# 04_SDRAM.net
KiCad netlist of a schematic drawn in Altium Designer
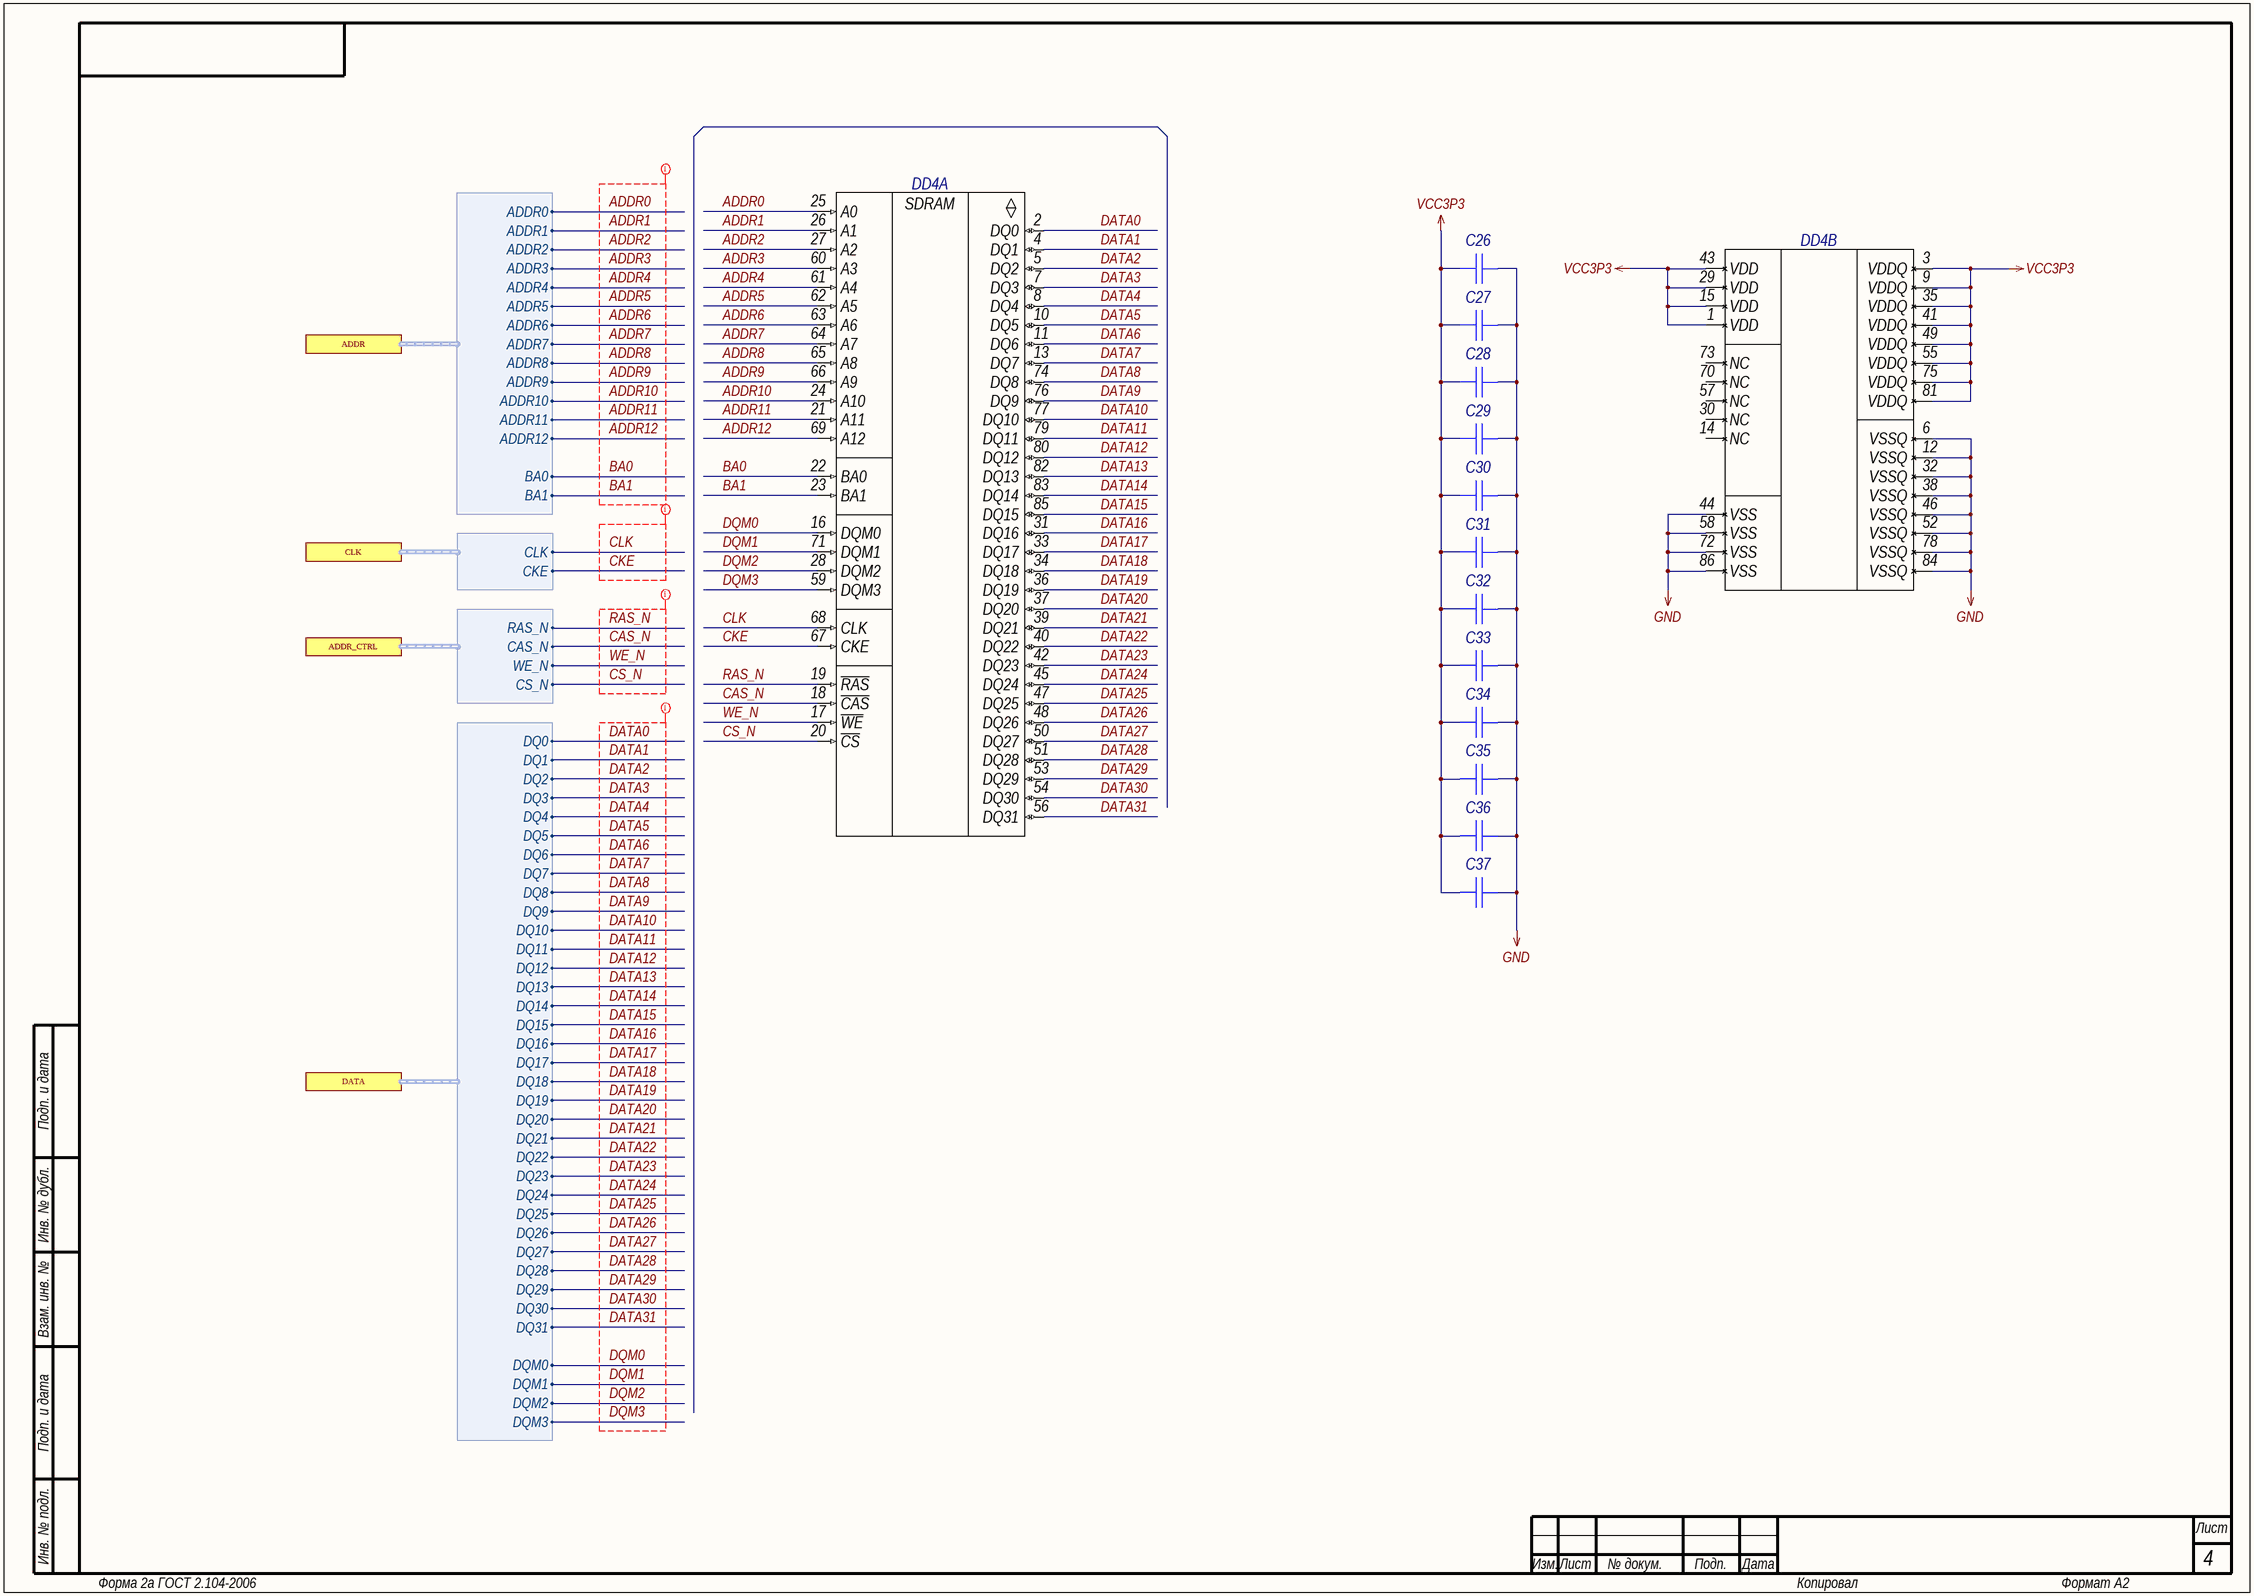
[diagram p0: 04_SDRAM.SchDoc]

(export (version "E")
  (design (tool "Eeschema 10.0.6"))
  (components
    (comp (ref "C26")
      (value "Capacitor")
      (footprint "C0402_L")
      (fields
        (field (name "PART NUMBER") "GRM155R60J106ME15D")
        (field (name "VOLTAGE") "6.3V")
        (field (name "TOLERANCE") "±20%")
        (field (name "PUBLISHER") "Andrew Danich")
      )
      (libsource (lib "ADLib") (part "Capacitor"))
    )
    (comp (ref "C27")
      (value "Capacitor")
      (footprint "C0402_L")
      (fields
        (field (name "PART NUMBER") "GRM155R60J106ME15D")
        (field (name "VOLTAGE") "6.3V")
        (field (name "TOLERANCE") "±20%")
        (field (name "PUBLISHER") "Andrew Danich")
      )
      (libsource (lib "ADLib") (part "Capacitor"))
    )
    (comp (ref "C28")
      (value "Capacitor")
      (footprint "C0402_L")
      (fields
        (field (name "PART NUMBER") "GCM155R71C104KA55D")
        (field (name "VOLTAGE") "16V")
        (field (name "TOLERANCE") "±10%")
        (field (name "PUBLISHER") "Andrew Danich")
      )
      (libsource (lib "ADLib") (part "Capacitor"))
    )
    (comp (ref "C29")
      (value "Capacitor")
      (footprint "C0402_L")
      (fields
        (field (name "PART NUMBER") "GCM155R71C104KA55D")
        (field (name "VOLTAGE") "16V")
        (field (name "TOLERANCE") "±10%")
        (field (name "PUBLISHER") "Andrew Danich")
      )
      (libsource (lib "ADLib") (part "Capacitor"))
    )
    (comp (ref "C30")
      (value "Capacitor")
      (footprint "C0402_L")
      (fields
        (field (name "PART NUMBER") "GCM155R71C104KA55D")
        (field (name "VOLTAGE") "16V")
        (field (name "TOLERANCE") "±10%")
        (field (name "PUBLISHER") "Andrew Danich")
      )
      (libsource (lib "ADLib") (part "Capacitor"))
    )
    (comp (ref "C31")
      (value "Capacitor")
      (footprint "C0402_L")
      (fields
        (field (name "PART NUMBER") "GCM155R71C104KA55D")
        (field (name "VOLTAGE") "16V")
        (field (name "TOLERANCE") "±10%")
        (field (name "PUBLISHER") "Andrew Danich")
      )
      (libsource (lib "ADLib") (part "Capacitor"))
    )
    (comp (ref "C32")
      (value "Capacitor")
      (footprint "C0402_L")
      (fields
        (field (name "PART NUMBER") "GCM155R71E103KA37D")
        (field (name "VOLTAGE") "25V")
        (field (name "TOLERANCE") "±10%")
        (field (name "PUBLISHER") "Andrew Danich")
      )
      (libsource (lib "ADLib") (part "Capacitor"))
    )
    (comp (ref "C33")
      (value "Capacitor")
      (footprint "C0402_L")
      (fields
        (field (name "PART NUMBER") "GCM155R71E103KA37D")
        (field (name "VOLTAGE") "25V")
        (field (name "TOLERANCE") "±10%")
        (field (name "PUBLISHER") "Andrew Danich")
      )
      (libsource (lib "ADLib") (part "Capacitor"))
    )
    (comp (ref "C34")
      (value "Capacitor")
      (footprint "C0402_L")
      (fields
        (field (name "PART NUMBER") "GCM155R71E103KA37D")
        (field (name "VOLTAGE") "25V")
        (field (name "TOLERANCE") "±10%")
        (field (name "PUBLISHER") "Andrew Danich")
      )
      (libsource (lib "ADLib") (part "Capacitor"))
    )
    (comp (ref "C35")
      (value "Capacitor")
      (footprint "C0402_L")
      (fields
        (field (name "PART NUMBER") "GCM155R71E103KA37D")
        (field (name "VOLTAGE") "25V")
        (field (name "TOLERANCE") "±10%")
        (field (name "PUBLISHER") "Andrew Danich")
      )
      (libsource (lib "ADLib") (part "Capacitor"))
    )
    (comp (ref "C36")
      (value "Capacitor")
      (footprint "C0402_L")
      (fields
        (field (name "PART NUMBER") "GCM155R71E103KA37D")
        (field (name "VOLTAGE") "25V")
        (field (name "TOLERANCE") "±10%")
        (field (name "PUBLISHER") "Andrew Danich")
      )
      (libsource (lib "ADLib") (part "Capacitor"))
    )
    (comp (ref "C37")
      (value "Capacitor")
      (footprint "C0402_L")
      (fields
        (field (name "PART NUMBER") "GCM155R71E103KA37D")
        (field (name "VOLTAGE") "25V")
        (field (name "TOLERANCE") "±10%")
        (field (name "PUBLISHER") "Andrew Danich")
      )
      (libsource (lib "ADLib") (part "Capacitor"))
    )
    (comp (ref "DD4")
      (value "IS4xS32160F-xTxx-Series")
      (footprint "TSOP2-86_050P2222X1016X125_N")
      (fields
        (field (name "PART NUMBER") "IS42S32160F-7TLI")
        (field (name "MANUFACTURER") "ISSI")
        (field (name "PUBLISHER") "Andrew Danich")
      )
      (libsource (lib "ADLib") (part "IS4xS32160F-xTxx-Series"))
    )
  )
  (nets
    (net (code "5") (name "/ADDR0") (class "Default")
      (node (ref "DD4") (pin "25") (pinfunction "A0_25") (pintype "input"))
    )
    (net (code "6") (name "/ADDR1") (class "Default")
      (node (ref "DD4") (pin "26") (pinfunction "A1_26") (pintype "input"))
    )
    (net (code "7") (name "/ADDR2") (class "Default")
      (node (ref "DD4") (pin "27") (pinfunction "A2_27") (pintype "input"))
    )
    (net (code "8") (name "/ADDR3") (class "Default")
      (node (ref "DD4") (pin "60") (pinfunction "A3_60") (pintype "input"))
    )
    (net (code "9") (name "/ADDR4") (class "Default")
      (node (ref "DD4") (pin "61") (pinfunction "A4_61") (pintype "input"))
    )
    (net (code "10") (name "/ADDR5") (class "Default")
      (node (ref "DD4") (pin "62") (pinfunction "A5_62") (pintype "input"))
    )
    (net (code "11") (name "/ADDR6") (class "Default")
      (node (ref "DD4") (pin "63") (pinfunction "A6_63") (pintype "input"))
    )
    (net (code "12") (name "/ADDR7") (class "Default")
      (node (ref "DD4") (pin "64") (pinfunction "A7_64") (pintype "input"))
    )
    (net (code "13") (name "/ADDR8") (class "Default")
      (node (ref "DD4") (pin "65") (pinfunction "A8_65") (pintype "input"))
    )
    (net (code "14") (name "/ADDR9") (class "Default")
      (node (ref "DD4") (pin "66") (pinfunction "A9_66") (pintype "input"))
    )
    (net (code "15") (name "/ADDR10") (class "Default")
      (node (ref "DD4") (pin "24") (pinfunction "A10_24") (pintype "input"))
    )
    (net (code "16") (name "/ADDR11") (class "Default")
      (node (ref "DD4") (pin "21") (pinfunction "A11_21") (pintype "input"))
    )
    (net (code "17") (name "/ADDR12") (class "Default")
      (node (ref "DD4") (pin "69") (pinfunction "A12_69") (pintype "input"))
    )
    (net (code "18") (name "/BA0") (class "Default")
      (node (ref "DD4") (pin "22") (pinfunction "BA0_22") (pintype "input"))
    )
    (net (code "19") (name "/BA1") (class "Default")
      (node (ref "DD4") (pin "23") (pinfunction "BA1_23") (pintype "input"))
    )
    (net (code "20") (name "/CAS_N") (class "Default")
      (node (ref "DD4") (pin "18") (pinfunction "~{CAS}_18") (pintype "input"))
    )
    (net (code "21") (name "/CKE") (class "Default")
      (node (ref "DD4") (pin "67") (pinfunction "CKE_67") (pintype "input"))
    )
    (net (code "22") (name "/CLK") (class "Default")
      (node (ref "DD4") (pin "68") (pinfunction "CLK_68") (pintype "input"))
    )
    (net (code "23") (name "/CS_N") (class "Default")
      (node (ref "DD4") (pin "20") (pinfunction "~{CS}_20") (pintype "input"))
    )
    (net (code "24") (name "/DATA0") (class "Default")
      (node (ref "DD4") (pin "2") (pinfunction "DQ0_2") (pintype "bidirectional"))
    )
    (net (code "25") (name "/DATA1") (class "Default")
      (node (ref "DD4") (pin "4") (pinfunction "DQ1_4") (pintype "bidirectional"))
    )
    (net (code "26") (name "/DATA2") (class "Default")
      (node (ref "DD4") (pin "5") (pinfunction "DQ2_5") (pintype "bidirectional"))
    )
    (net (code "27") (name "/DATA3") (class "Default")
      (node (ref "DD4") (pin "7") (pinfunction "DQ3_7") (pintype "bidirectional"))
    )
    (net (code "28") (name "/DATA4") (class "Default")
      (node (ref "DD4") (pin "8") (pinfunction "DQ4_8") (pintype "bidirectional"))
    )
    (net (code "29") (name "/DATA5") (class "Default")
      (node (ref "DD4") (pin "10") (pinfunction "DQ5_10") (pintype "bidirectional"))
    )
    (net (code "30") (name "/DATA6") (class "Default")
      (node (ref "DD4") (pin "11") (pinfunction "DQ6_11") (pintype "bidirectional"))
    )
    (net (code "31") (name "/DATA7") (class "Default")
      (node (ref "DD4") (pin "13") (pinfunction "DQ7_13") (pintype "bidirectional"))
    )
    (net (code "32") (name "/DATA8") (class "Default")
      (node (ref "DD4") (pin "74") (pinfunction "DQ8_74") (pintype "bidirectional"))
    )
    (net (code "33") (name "/DATA9") (class "Default")
      (node (ref "DD4") (pin "76") (pinfunction "DQ9_76") (pintype "bidirectional"))
    )
    (net (code "34") (name "/DATA10") (class "Default")
      (node (ref "DD4") (pin "77") (pinfunction "DQ10_77") (pintype "bidirectional"))
    )
    (net (code "35") (name "/DATA11") (class "Default")
      (node (ref "DD4") (pin "79") (pinfunction "DQ11_79") (pintype "bidirectional"))
    )
    (net (code "36") (name "/DATA12") (class "Default")
      (node (ref "DD4") (pin "80") (pinfunction "DQ12_80") (pintype "bidirectional"))
    )
    (net (code "37") (name "/DATA13") (class "Default")
      (node (ref "DD4") (pin "82") (pinfunction "DQ13_82") (pintype "bidirectional"))
    )
    (net (code "38") (name "/DATA14") (class "Default")
      (node (ref "DD4") (pin "83") (pinfunction "DQ14_83") (pintype "bidirectional"))
    )
    (net (code "39") (name "/DATA15") (class "Default")
      (node (ref "DD4") (pin "85") (pinfunction "DQ15_85") (pintype "bidirectional"))
    )
    (net (code "40") (name "/DATA16") (class "Default")
      (node (ref "DD4") (pin "31") (pinfunction "DQ16_31") (pintype "bidirectional"))
    )
    (net (code "41") (name "/DATA17") (class "Default")
      (node (ref "DD4") (pin "33") (pinfunction "DQ17_33") (pintype "bidirectional"))
    )
    (net (code "42") (name "/DATA18") (class "Default")
      (node (ref "DD4") (pin "34") (pinfunction "DQ18_34") (pintype "bidirectional"))
    )
    (net (code "43") (name "/DATA19") (class "Default")
      (node (ref "DD4") (pin "36") (pinfunction "DQ19_36") (pintype "bidirectional"))
    )
    (net (code "44") (name "/DATA20") (class "Default")
      (node (ref "DD4") (pin "37") (pinfunction "DQ20_37") (pintype "bidirectional"))
    )
    (net (code "45") (name "/DATA21") (class "Default")
      (node (ref "DD4") (pin "39") (pinfunction "DQ21_39") (pintype "bidirectional"))
    )
    (net (code "46") (name "/DATA22") (class "Default")
      (node (ref "DD4") (pin "40") (pinfunction "DQ22_40") (pintype "bidirectional"))
    )
    (net (code "47") (name "/DATA23") (class "Default")
      (node (ref "DD4") (pin "42") (pinfunction "DQ23_42") (pintype "bidirectional"))
    )
    (net (code "48") (name "/DATA24") (class "Default")
      (node (ref "DD4") (pin "45") (pinfunction "DQ24_45") (pintype "bidirectional"))
    )
    (net (code "49") (name "/DATA25") (class "Default")
      (node (ref "DD4") (pin "47") (pinfunction "DQ25_47") (pintype "bidirectional"))
    )
    (net (code "50") (name "/DATA26") (class "Default")
      (node (ref "DD4") (pin "48") (pinfunction "DQ26_48") (pintype "bidirectional"))
    )
    (net (code "51") (name "/DATA27") (class "Default")
      (node (ref "DD4") (pin "50") (pinfunction "DQ27_50") (pintype "bidirectional"))
    )
    (net (code "52") (name "/DATA28") (class "Default")
      (node (ref "DD4") (pin "51") (pinfunction "DQ28_51") (pintype "bidirectional"))
    )
    (net (code "53") (name "/DATA29") (class "Default")
      (node (ref "DD4") (pin "53") (pinfunction "DQ29_53") (pintype "bidirectional"))
    )
    (net (code "54") (name "/DATA30") (class "Default")
      (node (ref "DD4") (pin "54") (pinfunction "DQ30_54") (pintype "bidirectional"))
    )
    (net (code "55") (name "/DATA31") (class "Default")
      (node (ref "DD4") (pin "56") (pinfunction "DQ31_56") (pintype "bidirectional"))
    )
    (net (code "56") (name "/DQM0") (class "Default")
      (node (ref "DD4") (pin "16") (pinfunction "DQM0_16") (pintype "input"))
    )
    (net (code "57") (name "/DQM1") (class "Default")
      (node (ref "DD4") (pin "71") (pinfunction "DQM1_71") (pintype "input"))
    )
    (net (code "58") (name "/DQM2") (class "Default")
      (node (ref "DD4") (pin "28") (pinfunction "DQM2_28") (pintype "input"))
    )
    (net (code "59") (name "/DQM3") (class "Default")
      (node (ref "DD4") (pin "59") (pinfunction "DQM3_59") (pintype "input"))
    )
    (net (code "60") (name "/RAS_N") (class "Default")
      (node (ref "DD4") (pin "19") (pinfunction "~{RAS}_19") (pintype "input"))
    )
    (net (code "61") (name "/WE_N") (class "Default")
      (node (ref "DD4") (pin "17") (pinfunction "~{WE}_17") (pintype "input"))
    )
    (net (code "66") (name "GND") (class "Default")
      (node (ref "C26") (pin "2") (pinfunction "2_2") (pintype "passive"))
      (node (ref "C27") (pin "2") (pinfunction "2_2") (pintype "passive"))
      (node (ref "C28") (pin "2") (pinfunction "2_2") (pintype "passive"))
      (node (ref "C29") (pin "2") (pinfunction "2_2") (pintype "passive"))
      (node (ref "C30") (pin "2") (pinfunction "2_2") (pintype "passive"))
      (node (ref "C31") (pin "2") (pinfunction "2_2") (pintype "passive"))
      (node (ref "C32") (pin "2") (pinfunction "2_2") (pintype "passive"))
      (node (ref "C33") (pin "2") (pinfunction "2_2") (pintype "passive"))
      (node (ref "C34") (pin "2") (pinfunction "2_2") (pintype "passive"))
      (node (ref "C35") (pin "2") (pinfunction "2_2") (pintype "passive"))
      (node (ref "C36") (pin "2") (pinfunction "2_2") (pintype "passive"))
      (node (ref "C37") (pin "2") (pinfunction "2_2") (pintype "passive"))
      (node (ref "DD4") (pin "12") (pinfunction "VSSQ_12") (pintype "power_in"))
      (node (ref "DD4") (pin "32") (pinfunction "VSSQ_32") (pintype "power_in"))
      (node (ref "DD4") (pin "38") (pinfunction "VSSQ_38") (pintype "power_in"))
      (node (ref "DD4") (pin "44") (pinfunction "VSS_44") (pintype "power_in"))
      (node (ref "DD4") (pin "46") (pinfunction "VSSQ_46") (pintype "power_in"))
      (node (ref "DD4") (pin "52") (pinfunction "VSSQ_52") (pintype "power_in"))
      (node (ref "DD4") (pin "58") (pinfunction "VSS_58") (pintype "power_in"))
      (node (ref "DD4") (pin "6") (pinfunction "VSSQ_6") (pintype "power_in"))
      (node (ref "DD4") (pin "72") (pinfunction "VSS_72") (pintype "power_in"))
      (node (ref "DD4") (pin "78") (pinfunction "VSSQ_78") (pintype "power_in"))
      (node (ref "DD4") (pin "84") (pinfunction "VSSQ_84") (pintype "power_in"))
      (node (ref "DD4") (pin "86") (pinfunction "VSS_86") (pintype "power_in"))
    )
    (net (code "67") (name "VCC3P3") (class "Default")
      (node (ref "C26") (pin "1") (pinfunction "1_1") (pintype "passive"))
      (node (ref "C27") (pin "1") (pinfunction "1_1") (pintype "passive"))
      (node (ref "C28") (pin "1") (pinfunction "1_1") (pintype "passive"))
      (node (ref "C29") (pin "1") (pinfunction "1_1") (pintype "passive"))
      (node (ref "C30") (pin "1") (pinfunction "1_1") (pintype "passive"))
      (node (ref "C31") (pin "1") (pinfunction "1_1") (pintype "passive"))
      (node (ref "C32") (pin "1") (pinfunction "1_1") (pintype "passive"))
      (node (ref "C33") (pin "1") (pinfunction "1_1") (pintype "passive"))
      (node (ref "C34") (pin "1") (pinfunction "1_1") (pintype "passive"))
      (node (ref "C35") (pin "1") (pinfunction "1_1") (pintype "passive"))
      (node (ref "C36") (pin "1") (pinfunction "1_1") (pintype "passive"))
      (node (ref "C37") (pin "1") (pinfunction "1_1") (pintype "passive"))
      (node (ref "DD4") (pin "1") (pinfunction "VDD_1") (pintype "power_in"))
      (node (ref "DD4") (pin "15") (pinfunction "VDD_15") (pintype "power_in"))
      (node (ref "DD4") (pin "29") (pinfunction "VDD_29") (pintype "power_in"))
      (node (ref "DD4") (pin "3") (pinfunction "VDDQ_3") (pintype "power_in"))
      (node (ref "DD4") (pin "35") (pinfunction "VDDQ_35") (pintype "power_in"))
      (node (ref "DD4") (pin "41") (pinfunction "VDDQ_41") (pintype "power_in"))
      (node (ref "DD4") (pin "43") (pinfunction "VDD_43") (pintype "power_in"))
      (node (ref "DD4") (pin "49") (pinfunction "VDDQ_49") (pintype "power_in"))
      (node (ref "DD4") (pin "55") (pinfunction "VDDQ_55") (pintype "power_in"))
      (node (ref "DD4") (pin "75") (pinfunction "VDDQ_75") (pintype "power_in"))
      (node (ref "DD4") (pin "81") (pinfunction "VDDQ_81") (pintype "power_in"))
      (node (ref "DD4") (pin "9") (pinfunction "VDDQ_9") (pintype "power_in"))
    )
    (net (code "68") (name "unconnected-(DD4B-NC-Pad14)") (class "Default")
      (node (ref "DD4") (pin "14") (pinfunction "NC_14") (pintype "passive"))
    )
    (net (code "69") (name "unconnected-(DD4B-NC-Pad30)") (class "Default")
      (node (ref "DD4") (pin "30") (pinfunction "NC_30") (pintype "passive"))
    )
    (net (code "70") (name "unconnected-(DD4B-NC-Pad57)") (class "Default")
      (node (ref "DD4") (pin "57") (pinfunction "NC_57") (pintype "passive"))
    )
    (net (code "71") (name "unconnected-(DD4B-NC-Pad70)") (class "Default")
      (node (ref "DD4") (pin "70") (pinfunction "NC_70") (pintype "passive"))
    )
    (net (code "72") (name "unconnected-(DD4B-NC-Pad73)") (class "Default")
      (node (ref "DD4") (pin "73") (pinfunction "NC_73") (pintype "passive"))
    )
  )
)
